# 51_V3.net
KiCad netlist of a schematic drawn in EasyEDA Pro
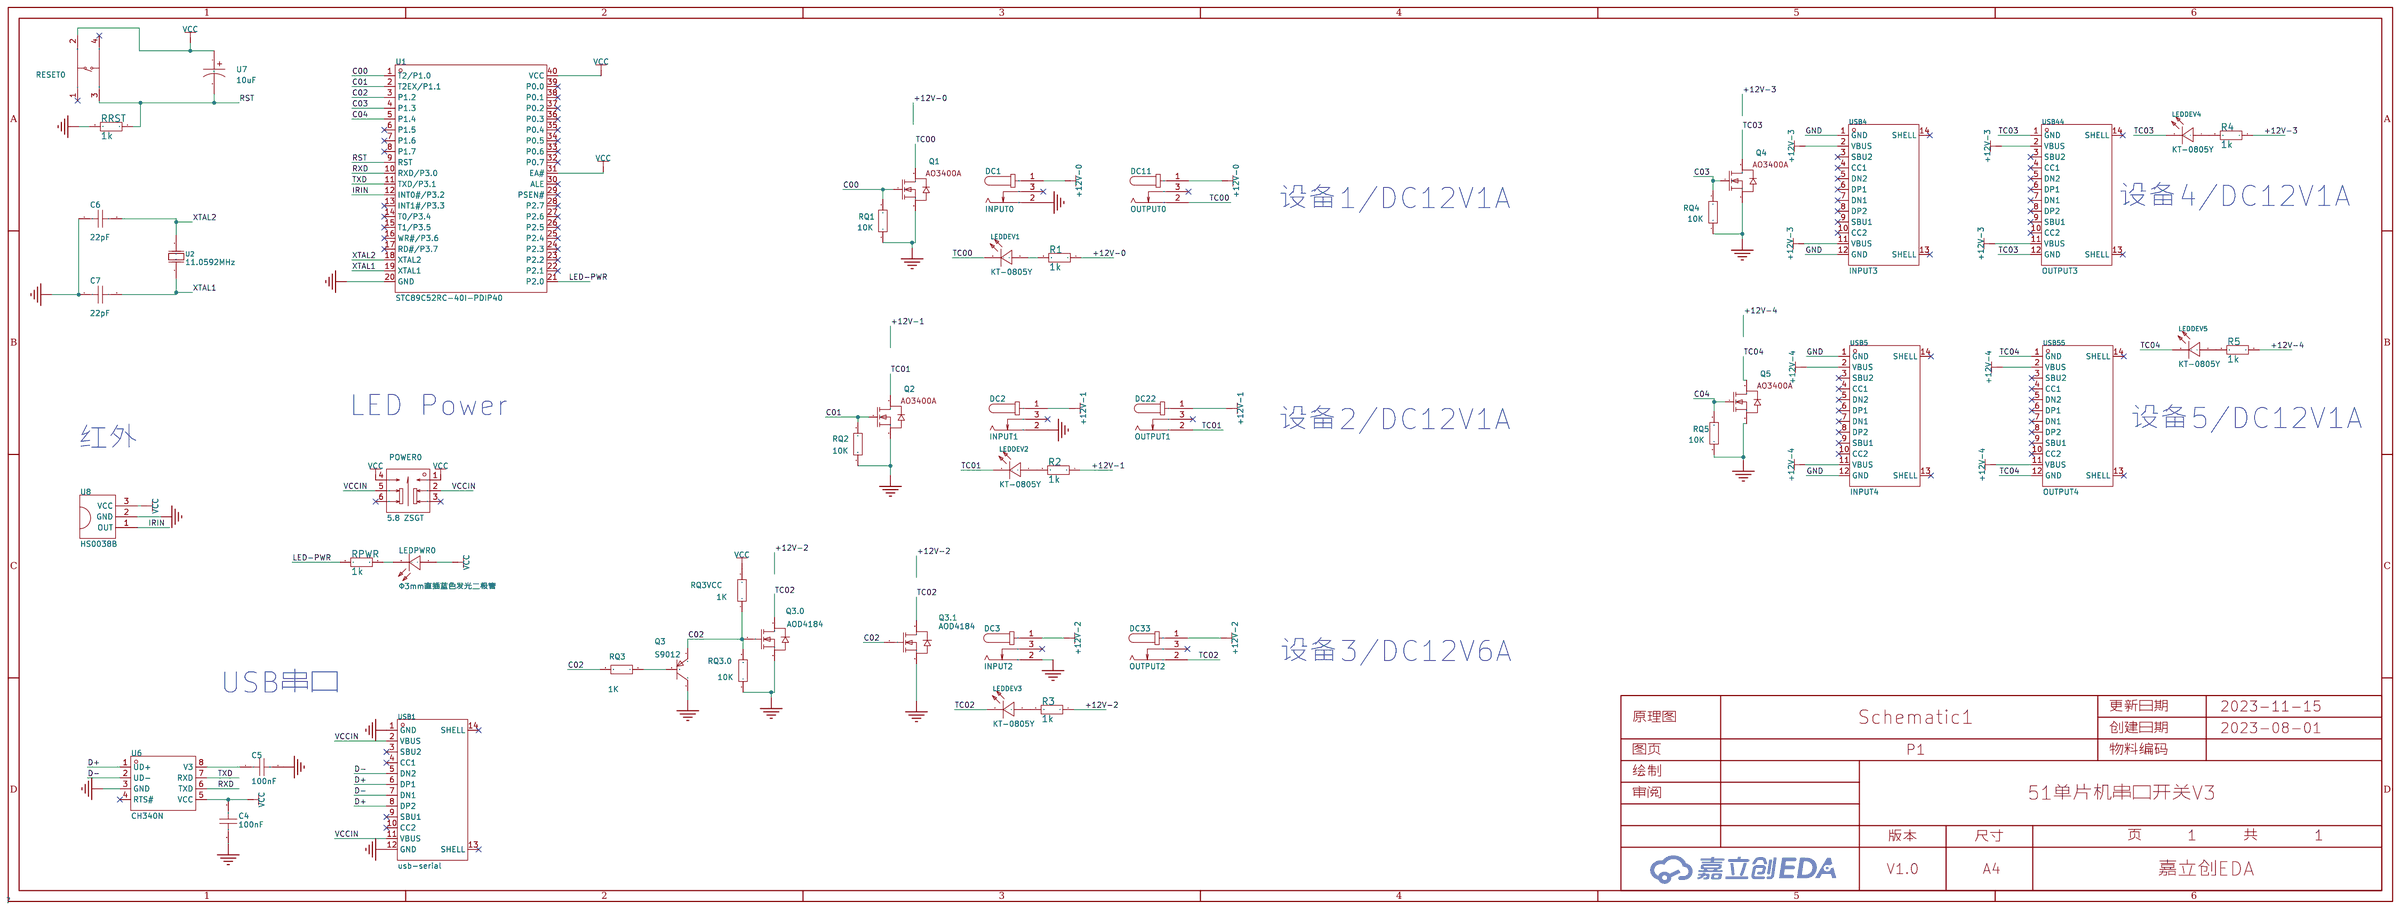
[diagram p0: schematic sheet]

(export (version "E")
  (design (tool "Eeschema 10.0.6"))
  (components
    (comp (ref "C4")
      (value "100nF")
      (footprint "easyedapro:C0603")
      (libsource (lib "easyedapro") (part "CapAcitance"))
    )
    (comp (ref "C5")
      (value "100nF")
      (footprint "easyedapro:C0603")
      (libsource (lib "easyedapro") (part "CapAcitance"))
    )
    (comp (ref "C6")
      (value "22pF")
      (footprint "easyedapro:CAP-TH_L5.8-W2.4-P2.54-D0.6")
      (description "容值:22pF;精度:±10%;额定电压:50V;温度系数:NP0;")
      (fields
        (field (name "Manufacturer Part") "CC1H220KA1EDCH4B1100")
        (field (name "Manufacturer") "Dersonic(德尔创)")
      )
      (libsource (lib "easyedapro") (part "CC1H220KA1EDCH4B1100"))
    )
    (comp (ref "C7")
      (value "22pF")
      (footprint "easyedapro:CAP-TH_L5.8-W2.4-P2.54-D0.6")
      (description "容值:22pF;精度:±10%;额定电压:50V;温度系数:NP0;")
      (fields
        (field (name "Manufacturer Part") "CC1H220KA1EDCH4B1100")
        (field (name "Manufacturer") "Dersonic(德尔创)")
      )
      (libsource (lib "easyedapro") (part "CC1H220KA1EDCH4B1100"))
    )
    (comp (ref "DC1")
      (value "INPUT0")
      (footprint "easyedapro:DC-IN-TH_DC-005-20A")
      (description "触点内径:2mm;触点外径:6.4mm;额定电流:500mA;额定电压:30V;")
      (fields (field (name "Manufacturer Part") "DC-005-20A") (field (name "Manufacturer") "韩国韩荣"))
      (libsource (lib "easyedapro") (part "DC-005-20A_C136744"))
    )
    (comp (ref "DC2")
      (value "INPUT1")
      (footprint "easyedapro:DC-IN-TH_DC-005-20A")
      (description "触点内径:2mm;触点外径:6.4mm;额定电流:500mA;额定电压:30V;")
      (fields (field (name "Manufacturer Part") "DC-005-20A") (field (name "Manufacturer") "韩国韩荣"))
      (libsource (lib "easyedapro") (part "DC-005-20A_C136744"))
    )
    (comp (ref "DC3")
      (value "INPUT2")
      (footprint "easyedapro:DC-IN-TH_DC-005-20A")
      (description "触点内径:2mm;触点外径:6.4mm;额定电流:500mA;额定电压:30V;")
      (fields (field (name "Manufacturer Part") "DC-005-20A") (field (name "Manufacturer") "韩国韩荣"))
      (libsource (lib "easyedapro") (part "DC-005-20A_C136744"))
    )
    (comp (ref "DC11")
      (value "OUTPUT0")
      (footprint "easyedapro:DC-IN-TH_DC-005-20A")
      (description "触点内径:2mm;触点外径:6.4mm;额定电流:500mA;额定电压:30V;")
      (fields (field (name "Manufacturer Part") "DC-005-20A") (field (name "Manufacturer") "韩国韩荣"))
      (libsource (lib "easyedapro") (part "DC-005-20A_C136744"))
    )
    (comp (ref "DC22")
      (value "OUTPUT1")
      (footprint "easyedapro:DC-IN-TH_DC-005-20A")
      (description "触点内径:2mm;触点外径:6.4mm;额定电流:500mA;额定电压:30V;")
      (fields (field (name "Manufacturer Part") "DC-005-20A") (field (name "Manufacturer") "韩国韩荣"))
      (libsource (lib "easyedapro") (part "DC-005-20A_C136744"))
    )
    (comp (ref "DC33")
      (value "OUTPUT2")
      (footprint "easyedapro:DC-IN-TH_DC-005-20A")
      (description "触点内径:2mm;触点外径:6.4mm;额定电流:500mA;额定电压:30V;")
      (fields (field (name "Manufacturer Part") "DC-005-20A") (field (name "Manufacturer") "韩国韩荣"))
      (libsource (lib "easyedapro") (part "DC-005-20A_C136744"))
    )
    (comp (ref "LEDDEV1")
      (value "KT-0805Y")
      (footprint "easyedapro:LED0805-R-RD")
      (description "发光颜色:黄灯;二极管配置:-;透镜颜色:-;主波长:-;色温:-;功率:-;发光角度:-;安装方式:-;工作温度:-;")
      (fields (field (name "Manufacturer") "KENTO"))
      (libsource (lib "easyedapro") (part "17-21SUYC/TR8"))
    )
    (comp (ref "LEDDEV2")
      (value "KT-0805Y")
      (footprint "easyedapro:LED0805-R-RD")
      (description "发光颜色:黄灯;二极管配置:-;透镜颜色:-;主波长:-;色温:-;功率:-;发光角度:-;安装方式:-;工作温度:-;")
      (fields (field (name "Manufacturer") "KENTO"))
      (libsource (lib "easyedapro") (part "17-21SUYC/TR8"))
    )
    (comp (ref "LEDDEV3")
      (value "KT-0805Y")
      (footprint "easyedapro:LED0805-R-RD")
      (description "发光颜色:黄灯;二极管配置:-;透镜颜色:-;主波长:-;色温:-;功率:-;发光角度:-;安装方式:-;工作温度:-;")
      (fields (field (name "Manufacturer") "KENTO"))
      (libsource (lib "easyedapro") (part "17-21SUYC/TR8"))
    )
    (comp (ref "LEDDEV4")
      (value "KT-0805Y")
      (footprint "easyedapro:LED0805-R-RD")
      (description "发光颜色:黄灯;二极管配置:-;透镜颜色:-;主波长:-;色温:-;功率:-;发光角度:-;安装方式:-;工作温度:-;")
      (fields (field (name "Manufacturer") "KENTO"))
      (libsource (lib "easyedapro") (part "17-21SUYC/TR8"))
    )
    (comp (ref "LEDDEV5")
      (value "KT-0805Y")
      (footprint "easyedapro:LED0805-R-RD")
      (description "发光颜色:黄灯;二极管配置:-;透镜颜色:-;主波长:-;色温:-;功率:-;发光角度:-;安装方式:-;工作温度:-;")
      (fields (field (name "Manufacturer") "KENTO"))
      (libsource (lib "easyedapro") (part "17-21SUYC/TR8"))
    )
    (comp (ref "LEDPWR0")
      (value "Φ3mm直插蓝色发光二极管")
      (footprint "easyedapro:LED-TH_BD4.1-P2.50-D0.5-FD_BULE")
      (libsource (lib "easyedapro") (part "Φ3MM直插蓝色发光二极管"))
    )
    (comp (ref "POWER0")
      (value "5.8 ZSGT")
      (footprint "easyedapro:SW-TH_5.8ZSGT")
      (fields (field (name "Manufacturer") "SHOU HAN(首韩)"))
      (libsource (lib "easyedapro") (part "5.8 ZSGT"))
    )
    (comp (ref "Q1")
      (value "AO3400A")
      (footprint "easyedapro:SOT-23-3_L2.9-W1.3-P1.90-LS2.4-BR")
      (description "类型:N沟道;漏源电压(Vdss):30V;连续漏极电流(Id):5.8A;功率(Pd):1.4W;导通电阻(RDS(on)@Vgs,Id):35mΩ@10V,5.8A;")
      (fields (field (name "Manufacturer Part") "AO3400A") (field (name "Manufacturer") "UMW(广东友台半导体)"))
      (libsource (lib "easyedapro") (part "AO3400A_C347475"))
    )
    (comp (ref "Q2")
      (value "AO3400A")
      (footprint "easyedapro:SOT-23-3_L2.9-W1.3-P1.90-LS2.4-BR")
      (description "类型:N沟道;漏源电压(Vdss):30V;连续漏极电流(Id):5.8A;功率(Pd):1.4W;导通电阻(RDS(on)@Vgs,Id):35mΩ@10V,5.8A;")
      (fields (field (name "Manufacturer Part") "AO3400A") (field (name "Manufacturer") "UMW(广东友台半导体)"))
      (libsource (lib "easyedapro") (part "AO3400A_C347475"))
    )
    (comp (ref "Q3")
      (value "S9012")
      (footprint "easyedapro:TO-92-3_L4.6-W3.6-P1.27-L-1")
      (fields (field (name "Manufacturer") "JSMSEMI(杰盛微)"))
      (libsource (lib "easyedapro") (part "S9012_C2931496"))
    )
    (comp (ref "Q3.0")
      (value "AOD4184")
      (footprint "easyedapro:TO-252-2_L6.6-W6.1-P4.58-LS9.9-BR")
      (fields (field (name "Manufacturer") "VBsemi(微碧)"))
      (libsource (lib "easyedapro") (part "AOD4184"))
    )
    (comp (ref "Q3.1")
      (value "AOD4184")
      (footprint "easyedapro:TO-252-2_L6.6-W6.1-P4.58-LS9.9-BR")
      (fields (field (name "Manufacturer") "VBsemi(微碧)"))
      (libsource (lib "easyedapro") (part "AOD4184"))
    )
    (comp (ref "Q4")
      (value "AO3400A")
      (footprint "easyedapro:SOT-23-3_L2.9-W1.3-P1.90-LS2.4-BR")
      (description "类型:N沟道;漏源电压(Vdss):30V;连续漏极电流(Id):5.8A;功率(Pd):1.4W;导通电阻(RDS(on)@Vgs,Id):35mΩ@10V,5.8A;")
      (fields (field (name "Manufacturer Part") "AO3400A") (field (name "Manufacturer") "UMW(广东友台半导体)"))
      (libsource (lib "easyedapro") (part "AO3400A_C347475"))
    )
    (comp (ref "Q5")
      (value "AO3400A")
      (footprint "easyedapro:SOT-23-3_L2.9-W1.3-P1.90-LS2.4-BR")
      (description "类型:N沟道;漏源电压(Vdss):30V;连续漏极电流(Id):5.8A;功率(Pd):1.4W;导通电阻(RDS(on)@Vgs,Id):35mΩ@10V,5.8A;")
      (fields (field (name "Manufacturer Part") "AO3400A") (field (name "Manufacturer") "UMW(广东友台半导体)"))
      (libsource (lib "easyedapro") (part "AO3400A_C347475"))
    )
    (comp (ref "R1")
      (value "1k")
      (footprint "easyedapro:0603")
      (description "Resistor")
      (libsource (lib "easyedapro") (part "RES"))
    )
    (comp (ref "R2")
      (value "1k")
      (footprint "easyedapro:0603")
      (description "Resistor")
      (libsource (lib "easyedapro") (part "RES"))
    )
    (comp (ref "R3")
      (value "1k")
      (footprint "easyedapro:0603")
      (description "Resistor")
      (libsource (lib "easyedapro") (part "RES"))
    )
    (comp (ref "R4")
      (value "1k")
      (footprint "easyedapro:0603")
      (description "Resistor")
      (libsource (lib "easyedapro") (part "RES"))
    )
    (comp (ref "R5")
      (value "1k")
      (footprint "easyedapro:0603")
      (description "Resistor")
      (libsource (lib "easyedapro") (part "RES"))
    )
    (comp (ref "RESET0")
      (value "TS665CJ")
      (footprint "easyedapro:SW-TH_4P-L6.0-W6.0-P4.50-LS6.5")
      (description "触点电流:50mA;额定电压(DC):12V;电路结构:单刀单掷;安装方式:直插;带灯:-;机械寿命:-;")
      (fields (field (name "Manufacturer") "SHOU HAN(首韩)"))
      (libsource (lib "easyedapro") (part "TS665CJ"))
    )
    (comp (ref "RPWR")
      (value "1k")
      (footprint "easyedapro:0603")
      (description "Resistor")
      (libsource (lib "easyedapro") (part "RES"))
    )
    (comp (ref "RQ1") (value "10K") (footprint "easyedapro:R0603") (libsource (lib "easyedapro") (part "电阻")))
    (comp (ref "RQ2") (value "10K") (footprint "easyedapro:R0603") (libsource (lib "easyedapro") (part "电阻")))
    (comp (ref "RQ3") (value "1K") (footprint "easyedapro:R0603") (libsource (lib "easyedapro") (part "电阻")))
    (comp (ref "RQ3.0")
      (value "10K")
      (footprint "easyedapro:R0603")
      (libsource (lib "easyedapro") (part "电阻"))
    )
    (comp (ref "RQ3VCC")
      (value "1K")
      (footprint "easyedapro:R0603")
      (libsource (lib "easyedapro") (part "电阻"))
    )
    (comp (ref "RQ4") (value "10K") (footprint "easyedapro:R0603") (libsource (lib "easyedapro") (part "电阻")))
    (comp (ref "RQ5") (value "10K") (footprint "easyedapro:R0603") (libsource (lib "easyedapro") (part "电阻")))
    (comp (ref "RRST")
      (value "1k")
      (footprint "easyedapro:0603")
      (description "Resistor")
      (libsource (lib "easyedapro") (part "RES"))
    )
    (comp (ref "U1")
      (value "STC89C52RC-40I-PDIP40")
      (footprint "easyedapro:DIP-40_L52.0-W13.7-P2.54-LS15.2-BL")
      (fields (field (name "Manufacturer") "STC(宏晶)"))
      (libsource (lib "easyedapro") (part "STC89C52RC-40I"))
    )
    (comp (ref "U2")
      (value "11.0592MHz")
      (footprint "easyedapro:CRYSTAL-TH_L10.8-W4.5-P4.88")
      (description "频率:10MHz;频率公差:±30ppm;负载电容:18pF;")
      (fields (field (name "Manufacturer Part") "ATS100B-E") (field (name "Manufacturer") "CTS(西迪斯)"))
      (libsource (lib "easyedapro") (part "ATS100B-E"))
    )
    (comp (ref "U6")
      (value "CH340N")
      (footprint "easyedapro:SOP-8_L4.9-W3.9-P1.27-LS6.0-BL")
      (fields (field (name "Manufacturer") "WCH(南京沁恒)"))
      (libsource (lib "easyedapro") (part "CH340N_C2977777"))
    )
    (comp (ref "U7")
      (value "10uF")
      (footprint "easyedapro:CAP-TH_BD6.3-P2.50-D0.5-FD")
      (description "容值:10uF;精度:±20%;额定电压:50V;纹波电流:-;等效串联电阻:-;")
      (fields
        (field (name "Manufacturer Part") "ESK106M1HD11RRSNP-R")
        (field (name "Manufacturer") "MAN YUE(万裕科技)")
      )
      (libsource (lib "easyedapro") (part "ESK106M1HD11RRSNP-R"))
    )
    (comp (ref "U8")
      (value "HS0038B")
      (footprint "easyedapro:OPTO-TH_HS0038B-A")
      (libsource (lib "easyedapro") (part "HS0038B"))
    )
    (comp (ref "USB1")
      (value "usb-serial")
      (footprint "easyedapro:USB-C-SMD_TYPE-C-6PIN-2MD-073")
      (description "连接器类型:Type-C;标准:-;公母:母座;触点数量:16;端口数量:1;安装方式:卧贴;额定电流 - 电源:5A;工作温度范围:-25°C~+85°C;")
      (fields
        (field (name "Manufacturer Part") "TYPE-C 16PIN 2MD(073)")
        (field (name "Manufacturer") "SHOU HAN(首韩)")
      )
      (libsource (lib "easyedapro") (part "TYPE-C 16PIN 2MD(073)"))
    )
    (comp (ref "USB4")
      (value "INPUT3")
      (footprint "easyedapro:USB-C-SMD_TYPE-C-6PIN-2MD-073")
      (description "连接器类型:Type-C;标准:-;公母:母座;触点数量:16;端口数量:1;安装方式:卧贴;额定电流 - 电源:5A;工作温度范围:-25°C~+85°C;")
      (fields
        (field (name "Manufacturer Part") "TYPE-C 16PIN 2MD(073)")
        (field (name "Manufacturer") "SHOU HAN(首韩)")
      )
      (libsource (lib "easyedapro") (part "TYPE-C 16PIN 2MD(073)"))
    )
    (comp (ref "USB5")
      (value "INPUT4")
      (footprint "easyedapro:USB-C-SMD_TYPE-C-6PIN-2MD-073")
      (description "连接器类型:Type-C;标准:-;公母:母座;触点数量:16;端口数量:1;安装方式:卧贴;额定电流 - 电源:5A;工作温度范围:-25°C~+85°C;")
      (fields
        (field (name "Manufacturer Part") "TYPE-C 16PIN 2MD(073)")
        (field (name "Manufacturer") "SHOU HAN(首韩)")
      )
      (libsource (lib "easyedapro") (part "TYPE-C 16PIN 2MD(073)"))
    )
    (comp (ref "USB44")
      (value "OUTPUT3")
      (footprint "easyedapro:USB-C-SMD_TYPE-C-6PIN-2MD-073")
      (description "连接器类型:Type-C;标准:-;公母:母座;触点数量:16;端口数量:1;安装方式:卧贴;额定电流 - 电源:5A;工作温度范围:-25°C~+85°C;")
      (fields
        (field (name "Manufacturer Part") "TYPE-C 16PIN 2MD(073)")
        (field (name "Manufacturer") "SHOU HAN(首韩)")
      )
      (libsource (lib "easyedapro") (part "TYPE-C 16PIN 2MD(073)"))
    )
    (comp (ref "USB55")
      (value "OUTPUT4")
      (footprint "easyedapro:USB-C-SMD_TYPE-C-6PIN-2MD-073")
      (description "连接器类型:Type-C;标准:-;公母:母座;触点数量:16;端口数量:1;安装方式:卧贴;额定电流 - 电源:5A;工作温度范围:-25°C~+85°C;")
      (fields
        (field (name "Manufacturer Part") "TYPE-C 16PIN 2MD(073)")
        (field (name "Manufacturer") "SHOU HAN(首韩)")
      )
      (libsource (lib "easyedapro") (part "TYPE-C 16PIN 2MD(073)"))
    )
  )
  (nets
    (net (code "1") (name "+12V-0") (class "Default")
      (node (ref "DC1") (pin "1") (pinfunction "1_1") (pintype "input"))
      (node (ref "DC11") (pin "1") (pinfunction "1_1") (pintype "input"))
      (node (ref "R1") (pin "1") (pinfunction "1_1") (pintype "input"))
    )
    (net (code "2") (name "+12V-1") (class "Default")
      (node (ref "DC2") (pin "1") (pinfunction "1_1") (pintype "input"))
      (node (ref "DC22") (pin "1") (pinfunction "1_1") (pintype "input"))
      (node (ref "R2") (pin "1") (pinfunction "1_1") (pintype "input"))
    )
    (net (code "3") (name "+12V-2") (class "Default")
      (node (ref "DC3") (pin "1") (pinfunction "1_1") (pintype "input"))
      (node (ref "DC33") (pin "1") (pinfunction "1_1") (pintype "input"))
      (node (ref "R3") (pin "1") (pinfunction "1_1") (pintype "input"))
    )
    (net (code "4") (name "+12V-3") (class "Default")
      (node (ref "R4") (pin "1") (pinfunction "1_1") (pintype "input"))
      (node (ref "USB4") (pin "11") (pinfunction "VBUS_11") (pintype "input"))
      (node (ref "USB4") (pin "2") (pinfunction "VBUS_2") (pintype "input"))
      (node (ref "USB44") (pin "11") (pinfunction "VBUS_11") (pintype "input"))
      (node (ref "USB44") (pin "2") (pinfunction "VBUS_2") (pintype "input"))
    )
    (net (code "5") (name "+12V-4") (class "Default")
      (node (ref "R5") (pin "1") (pinfunction "1_1") (pintype "input"))
      (node (ref "USB5") (pin "11") (pinfunction "VBUS_11") (pintype "input"))
      (node (ref "USB5") (pin "2") (pinfunction "VBUS_2") (pintype "input"))
      (node (ref "USB55") (pin "11") (pinfunction "VBUS_11") (pintype "input"))
      (node (ref "USB55") (pin "2") (pinfunction "VBUS_2") (pintype "input"))
    )
    (net (code "6") (name "/C00") (class "Default")
      (node (ref "Q1") (pin "1") (pinfunction "G_1") (pintype "input"))
      (node (ref "RQ1") (pin "2") (pinfunction "2_2") (pintype "input"))
      (node (ref "U1") (pin "1") (pinfunction "T2/P1.0_1") (pintype "input"))
    )
    (net (code "7") (name "/C01") (class "Default")
      (node (ref "Q2") (pin "1") (pinfunction "G_1") (pintype "input"))
      (node (ref "RQ2") (pin "2") (pinfunction "2_2") (pintype "input"))
      (node (ref "U1") (pin "2") (pinfunction "T2EX/P1.1_2") (pintype "input"))
    )
    (net (code "8") (name "/C02") (class "Default")
      (node (ref "Q3") (pin "1") (pinfunction "E_1") (pintype "input"))
      (node (ref "Q3.0") (pin "1") (pinfunction "G_1") (pintype "input"))
      (node (ref "Q3.1") (pin "1") (pinfunction "G_1") (pintype "input"))
      (node (ref "RQ3") (pin "2") (pinfunction "2_2") (pintype "input"))
      (node (ref "RQ3.0") (pin "2") (pinfunction "2_2") (pintype "input"))
      (node (ref "RQ3VCC") (pin "1") (pinfunction "1_1") (pintype "input"))
      (node (ref "U1") (pin "3") (pinfunction "P1.2_3") (pintype "input"))
    )
    (net (code "9") (name "/C03") (class "Default")
      (node (ref "Q4") (pin "1") (pinfunction "G_1") (pintype "input"))
      (node (ref "RQ4") (pin "2") (pinfunction "2_2") (pintype "input"))
      (node (ref "U1") (pin "4") (pinfunction "P1.3_4") (pintype "input"))
    )
    (net (code "10") (name "/C04") (class "Default")
      (node (ref "Q5") (pin "1") (pinfunction "G_1") (pintype "input"))
      (node (ref "RQ5") (pin "2") (pinfunction "2_2") (pintype "input"))
      (node (ref "U1") (pin "5") (pinfunction "P1.4_5") (pintype "input"))
    )
    (net (code "11") (name "/D+") (class "Default")
      (node (ref "U6") (pin "1") (pinfunction "UD+_1") (pintype "input"))
      (node (ref "USB1") (pin "6") (pinfunction "DP1_6") (pintype "input"))
      (node (ref "USB1") (pin "8") (pinfunction "DP2_8") (pintype "input"))
    )
    (net (code "12") (name "/D-") (class "Default")
      (node (ref "U6") (pin "2") (pinfunction "UD-_2") (pintype "input"))
      (node (ref "USB1") (pin "5") (pinfunction "DN2_5") (pintype "input"))
      (node (ref "USB1") (pin "7") (pinfunction "DN1_7") (pintype "input"))
    )
    (net (code "13") (name "/IRIN") (class "Default")
      (node (ref "U1") (pin "12") (pinfunction "INT0#/P3.2_12") (pintype "input"))
      (node (ref "U8") (pin "1") (pinfunction "OUT_1") (pintype "input"))
    )
    (net (code "14") (name "/LED-PWR") (class "Default")
      (node (ref "RPWR") (pin "2") (pinfunction "2_2") (pintype "input"))
      (node (ref "U1") (pin "21") (pinfunction "P2.0_21") (pintype "input"))
    )
    (net (code "15") (name "/RST") (class "Default")
      (node (ref "RESET0") (pin "3") (pinfunction "C_3") (pintype "input"))
      (node (ref "RRST") (pin "1") (pinfunction "1_1") (pintype "input"))
      (node (ref "U1") (pin "9") (pinfunction "RST_9") (pintype "input"))
      (node (ref "U7") (pin "2") (pinfunction "2_2") (pintype "input"))
    )
    (net (code "16") (name "/RXD") (class "Default")
      (node (ref "U1") (pin "10") (pinfunction "RXD/P3.0_10") (pintype "input"))
      (node (ref "U6") (pin "6") (pinfunction "TXD_6") (pintype "input"))
    )
    (net (code "17") (name "/TC00") (class "Default")
      (node (ref "DC11") (pin "2") (pinfunction "2_2") (pintype "input"))
      (node (ref "LEDDEV1") (pin "2") (pinfunction "-_2") (pintype "input"))
      (node (ref "Q1") (pin "3") (pinfunction "D_3") (pintype "input"))
    )
    (net (code "18") (name "/TC01") (class "Default")
      (node (ref "DC22") (pin "2") (pinfunction "2_2") (pintype "input"))
      (node (ref "LEDDEV2") (pin "2") (pinfunction "-_2") (pintype "input"))
      (node (ref "Q2") (pin "3") (pinfunction "D_3") (pintype "input"))
    )
    (net (code "19") (name "/TC02") (class "Default")
      (node (ref "DC33") (pin "2") (pinfunction "2_2") (pintype "input"))
      (node (ref "LEDDEV3") (pin "2") (pinfunction "-_2") (pintype "input"))
      (node (ref "Q3.0") (pin "2") (pinfunction "D_2") (pintype "input"))
      (node (ref "Q3.1") (pin "2") (pinfunction "D_2") (pintype "input"))
    )
    (net (code "20") (name "/TC03") (class "Default")
      (node (ref "LEDDEV4") (pin "2") (pinfunction "-_2") (pintype "input"))
      (node (ref "Q4") (pin "3") (pinfunction "D_3") (pintype "input"))
      (node (ref "USB44") (pin "1") (pinfunction "GND_1") (pintype "input"))
      (node (ref "USB44") (pin "12") (pinfunction "GND_12") (pintype "input"))
    )
    (net (code "21") (name "/TC04") (class "Default")
      (node (ref "LEDDEV5") (pin "2") (pinfunction "-_2") (pintype "input"))
      (node (ref "Q5") (pin "3") (pinfunction "D_3") (pintype "input"))
      (node (ref "USB55") (pin "1") (pinfunction "GND_1") (pintype "input"))
      (node (ref "USB55") (pin "12") (pinfunction "GND_12") (pintype "input"))
    )
    (net (code "22") (name "/TXD") (class "Default")
      (node (ref "U1") (pin "11") (pinfunction "TXD/P3.1_11") (pintype "input"))
      (node (ref "U6") (pin "7") (pinfunction "RXD_7") (pintype "input"))
    )
    (net (code "23") (name "/VCCIN") (class "Default")
      (node (ref "POWER0") (pin "2") (pinfunction "2_2") (pintype "input"))
      (node (ref "POWER0") (pin "5") (pinfunction "5_5") (pintype "input"))
      (node (ref "USB1") (pin "11") (pinfunction "VBUS_11") (pintype "input"))
      (node (ref "USB1") (pin "2") (pinfunction "VBUS_2") (pintype "input"))
    )
    (net (code "24") (name "/XTAL1") (class "Default")
      (node (ref "C7") (pin "2") (pinfunction "2_2") (pintype "input"))
      (node (ref "U1") (pin "19") (pinfunction "XTAL1_19") (pintype "input"))
      (node (ref "U2") (pin "2") (pinfunction "2_2") (pintype "input"))
    )
    (net (code "25") (name "/XTAL2") (class "Default")
      (node (ref "C6") (pin "2") (pinfunction "2_2") (pintype "input"))
      (node (ref "U1") (pin "18") (pinfunction "XTAL2_18") (pintype "input"))
      (node (ref "U2") (pin "1") (pinfunction "1_1") (pintype "input"))
    )
    (net (code "26") (name "GND") (class "Default")
      (node (ref "C4") (pin "2") (pinfunction "2_2") (pintype "input"))
      (node (ref "C5") (pin "2") (pinfunction "2_2") (pintype "input"))
      (node (ref "C6") (pin "1") (pinfunction "1_1") (pintype "input"))
      (node (ref "C7") (pin "1") (pinfunction "1_1") (pintype "input"))
      (node (ref "DC1") (pin "2") (pinfunction "2_2") (pintype "input"))
      (node (ref "DC2") (pin "2") (pinfunction "2_2") (pintype "input"))
      (node (ref "DC3") (pin "2") (pinfunction "2_2") (pintype "input"))
      (node (ref "Q1") (pin "2") (pinfunction "S_2") (pintype "input"))
      (node (ref "Q2") (pin "2") (pinfunction "S_2") (pintype "input"))
      (node (ref "Q3") (pin "3") (pinfunction "C_3") (pintype "input"))
      (node (ref "Q3.0") (pin "3") (pinfunction "S_3") (pintype "input"))
      (node (ref "Q3.1") (pin "3") (pinfunction "S_3") (pintype "input"))
      (node (ref "Q4") (pin "2") (pinfunction "S_2") (pintype "input"))
      (node (ref "Q5") (pin "2") (pinfunction "S_2") (pintype "input"))
      (node (ref "RQ1") (pin "1") (pinfunction "1_1") (pintype "input"))
      (node (ref "RQ2") (pin "1") (pinfunction "1_1") (pintype "input"))
      (node (ref "RQ3.0") (pin "1") (pinfunction "1_1") (pintype "input"))
      (node (ref "RQ4") (pin "1") (pinfunction "1_1") (pintype "input"))
      (node (ref "RQ5") (pin "1") (pinfunction "1_1") (pintype "input"))
      (node (ref "RRST") (pin "2") (pinfunction "2_2") (pintype "input"))
      (node (ref "U1") (pin "20") (pinfunction "GND_20") (pintype "input"))
      (node (ref "U6") (pin "3") (pinfunction "GND_3") (pintype "input"))
      (node (ref "U8") (pin "2") (pinfunction "GND_2") (pintype "input"))
      (node (ref "USB1") (pin "1") (pinfunction "GND_1") (pintype "input"))
      (node (ref "USB1") (pin "12") (pinfunction "GND_12") (pintype "input"))
      (node (ref "USB4") (pin "1") (pinfunction "GND_1") (pintype "input"))
      (node (ref "USB4") (pin "12") (pinfunction "GND_12") (pintype "input"))
      (node (ref "USB5") (pin "1") (pinfunction "GND_1") (pintype "input"))
      (node (ref "USB5") (pin "12") (pinfunction "GND_12") (pintype "input"))
    )
    (net (code "27") (name "Net-(LEDDEV1-+)") (class "Default")
      (node (ref "LEDDEV1") (pin "1") (pinfunction "+_1") (pintype "input"))
      (node (ref "R1") (pin "2") (pinfunction "2_2") (pintype "input"))
    )
    (net (code "28") (name "Net-(LEDDEV2-+)") (class "Default")
      (node (ref "LEDDEV2") (pin "1") (pinfunction "+_1") (pintype "input"))
      (node (ref "R2") (pin "2") (pinfunction "2_2") (pintype "input"))
    )
    (net (code "29") (name "Net-(LEDDEV3-+)") (class "Default")
      (node (ref "LEDDEV3") (pin "1") (pinfunction "+_1") (pintype "input"))
      (node (ref "R3") (pin "2") (pinfunction "2_2") (pintype "input"))
    )
    (net (code "30") (name "Net-(LEDDEV4-+)") (class "Default")
      (node (ref "LEDDEV4") (pin "1") (pinfunction "+_1") (pintype "input"))
      (node (ref "R4") (pin "2") (pinfunction "2_2") (pintype "input"))
    )
    (net (code "31") (name "Net-(LEDDEV5-+)") (class "Default")
      (node (ref "LEDDEV5") (pin "1") (pinfunction "+_1") (pintype "input"))
      (node (ref "R5") (pin "2") (pinfunction "2_2") (pintype "input"))
    )
    (net (code "32") (name "Net-(LEDPWR0--)") (class "Default")
      (node (ref "LEDPWR0") (pin "2") (pinfunction "-_2") (pintype "input"))
      (node (ref "RPWR") (pin "1") (pinfunction "1_1") (pintype "input"))
    )
    (net (code "33") (name "Net-(Q3-B)") (class "Default")
      (node (ref "Q3") (pin "2") (pinfunction "B_2") (pintype "input"))
      (node (ref "RQ3") (pin "1") (pinfunction "1_1") (pintype "input"))
    )
    (net (code "34") (name "Net-(U6-V3)") (class "Default")
      (node (ref "C5") (pin "1") (pinfunction "1_1") (pintype "input"))
      (node (ref "U6") (pin "8") (pinfunction "V3_8") (pintype "input"))
    )
    (net (code "35") (name "VCC") (class "Default")
      (node (ref "C4") (pin "1") (pinfunction "1_1") (pintype "input"))
      (node (ref "LEDPWR0") (pin "1") (pinfunction "+_1") (pintype "input"))
      (node (ref "POWER0") (pin "1") (pinfunction "1_1") (pintype "input"))
      (node (ref "POWER0") (pin "4") (pinfunction "4_4") (pintype "input"))
      (node (ref "RESET0") (pin "2") (pinfunction "B_2") (pintype "input"))
      (node (ref "RQ3VCC") (pin "2") (pinfunction "2_2") (pintype "input"))
      (node (ref "U1") (pin "31") (pinfunction "EA#_31") (pintype "input"))
      (node (ref "U1") (pin "40") (pinfunction "VCC_40") (pintype "input"))
      (node (ref "U6") (pin "5") (pinfunction "VCC_5") (pintype "input"))
      (node (ref "U7") (pin "1") (pinfunction "1_1") (pintype "input"))
      (node (ref "U8") (pin "3") (pinfunction "VCC_3") (pintype "input"))
    )
    (net (code "36") (name "unconnected-(DC1-Pad3)") (class "Default")
      (node (ref "DC1") (pin "3") (pinfunction "3_3") (pintype "input+no_connect"))
    )
    (net (code "37") (name "unconnected-(DC2-Pad3)") (class "Default")
      (node (ref "DC2") (pin "3") (pinfunction "3_3") (pintype "input+no_connect"))
    )
    (net (code "38") (name "unconnected-(DC3-Pad3)") (class "Default")
      (node (ref "DC3") (pin "3") (pinfunction "3_3") (pintype "input+no_connect"))
    )
    (net (code "39") (name "unconnected-(DC11-Pad3)") (class "Default")
      (node (ref "DC11") (pin "3") (pinfunction "3_3") (pintype "input+no_connect"))
    )
    (net (code "40") (name "unconnected-(DC22-Pad3)") (class "Default")
      (node (ref "DC22") (pin "3") (pinfunction "3_3") (pintype "input+no_connect"))
    )
    (net (code "41") (name "unconnected-(DC33-Pad3)") (class "Default")
      (node (ref "DC33") (pin "3") (pinfunction "3_3") (pintype "input+no_connect"))
    )
    (net (code "42") (name "unconnected-(POWER0-Pad3)") (class "Default")
      (node (ref "POWER0") (pin "3") (pinfunction "3_3") (pintype "input+no_connect"))
    )
    (net (code "43") (name "unconnected-(POWER0-Pad6)") (class "Default")
      (node (ref "POWER0") (pin "6") (pinfunction "6_6") (pintype "input+no_connect"))
    )
    (net (code "44") (name "unconnected-(RESET0-A-Pad1)") (class "Default")
      (node (ref "RESET0") (pin "1") (pinfunction "A_1") (pintype "input+no_connect"))
    )
    (net (code "45") (name "unconnected-(RESET0-D-Pad4)") (class "Default")
      (node (ref "RESET0") (pin "4") (pinfunction "D_4") (pintype "input+no_connect"))
    )
    (net (code "46") (name "unconnected-(U1-ALE-Pad30)") (class "Default")
      (node (ref "U1") (pin "30") (pinfunction "ALE_30") (pintype "input+no_connect"))
    )
    (net (code "47") (name "unconnected-(U1-INT1#{slash}P3.3-Pad13)") (class "Default")
      (node (ref "U1") (pin "13") (pinfunction "INT1#/P3.3_13") (pintype "input+no_connect"))
    )
    (net (code "48") (name "unconnected-(U1-P0.0-Pad39)") (class "Default")
      (node (ref "U1") (pin "39") (pinfunction "P0.0_39") (pintype "input+no_connect"))
    )
    (net (code "49") (name "unconnected-(U1-P0.1-Pad38)") (class "Default")
      (node (ref "U1") (pin "38") (pinfunction "P0.1_38") (pintype "input+no_connect"))
    )
    (net (code "50") (name "unconnected-(U1-P0.2-Pad37)") (class "Default")
      (node (ref "U1") (pin "37") (pinfunction "P0.2_37") (pintype "input+no_connect"))
    )
    (net (code "51") (name "unconnected-(U1-P0.3-Pad36)") (class "Default")
      (node (ref "U1") (pin "36") (pinfunction "P0.3_36") (pintype "input+no_connect"))
    )
    (net (code "52") (name "unconnected-(U1-P0.4-Pad35)") (class "Default")
      (node (ref "U1") (pin "35") (pinfunction "P0.4_35") (pintype "input+no_connect"))
    )
    (net (code "53") (name "unconnected-(U1-P0.5-Pad34)") (class "Default")
      (node (ref "U1") (pin "34") (pinfunction "P0.5_34") (pintype "input+no_connect"))
    )
    (net (code "54") (name "unconnected-(U1-P0.6-Pad33)") (class "Default")
      (node (ref "U1") (pin "33") (pinfunction "P0.6_33") (pintype "input+no_connect"))
    )
    (net (code "55") (name "unconnected-(U1-P0.7-Pad32)") (class "Default")
      (node (ref "U1") (pin "32") (pinfunction "P0.7_32") (pintype "input+no_connect"))
    )
    (net (code "56") (name "unconnected-(U1-P1.5-Pad6)") (class "Default")
      (node (ref "U1") (pin "6") (pinfunction "P1.5_6") (pintype "input+no_connect"))
    )
    (net (code "57") (name "unconnected-(U1-P1.6-Pad7)") (class "Default")
      (node (ref "U1") (pin "7") (pinfunction "P1.6_7") (pintype "input+no_connect"))
    )
    (net (code "58") (name "unconnected-(U1-P1.7-Pad8)") (class "Default")
      (node (ref "U1") (pin "8") (pinfunction "P1.7_8") (pintype "input+no_connect"))
    )
    (net (code "59") (name "unconnected-(U1-P2.1-Pad22)") (class "Default")
      (node (ref "U1") (pin "22") (pinfunction "P2.1_22") (pintype "input+no_connect"))
    )
    (net (code "60") (name "unconnected-(U1-P2.2-Pad23)") (class "Default")
      (node (ref "U1") (pin "23") (pinfunction "P2.2_23") (pintype "input+no_connect"))
    )
    (net (code "61") (name "unconnected-(U1-P2.3-Pad24)") (class "Default")
      (node (ref "U1") (pin "24") (pinfunction "P2.3_24") (pintype "input+no_connect"))
    )
    (net (code "62") (name "unconnected-(U1-P2.4-Pad25)") (class "Default")
      (node (ref "U1") (pin "25") (pinfunction "P2.4_25") (pintype "input+no_connect"))
    )
    (net (code "63") (name "unconnected-(U1-P2.5-Pad26)") (class "Default")
      (node (ref "U1") (pin "26") (pinfunction "P2.5_26") (pintype "input+no_connect"))
    )
    (net (code "64") (name "unconnected-(U1-P2.6-Pad27)") (class "Default")
      (node (ref "U1") (pin "27") (pinfunction "P2.6_27") (pintype "input+no_connect"))
    )
    (net (code "65") (name "unconnected-(U1-P2.7-Pad28)") (class "Default")
      (node (ref "U1") (pin "28") (pinfunction "P2.7_28") (pintype "input+no_connect"))
    )
    (net (code "66") (name "unconnected-(U1-PSEN#-Pad29)") (class "Default")
      (node (ref "U1") (pin "29") (pinfunction "PSEN#_29") (pintype "input+no_connect"))
    )
    (net (code "67") (name "unconnected-(U1-RD#{slash}P3.7-Pad17)") (class "Default")
      (node (ref "U1") (pin "17") (pinfunction "RD#/P3.7_17") (pintype "input+no_connect"))
    )
    (net (code "68") (name "unconnected-(U1-T0{slash}P3.4-Pad14)") (class "Default")
      (node (ref "U1") (pin "14") (pinfunction "T0/P3.4_14") (pintype "input+no_connect"))
    )
    (net (code "69") (name "unconnected-(U1-T1{slash}P3.5-Pad15)") (class "Default")
      (node (ref "U1") (pin "15") (pinfunction "T1/P3.5_15") (pintype "input+no_connect"))
    )
    (net (code "70") (name "unconnected-(U1-WR#{slash}P3.6-Pad16)") (class "Default")
      (node (ref "U1") (pin "16") (pinfunction "WR#/P3.6_16") (pintype "input+no_connect"))
    )
    (net (code "71") (name "unconnected-(U6-RTS#-Pad4)") (class "Default")
      (node (ref "U6") (pin "4") (pinfunction "RTS#_4") (pintype "input+no_connect"))
    )
    (net (code "72") (name "unconnected-(USB1-CC1-Pad4)") (class "Default")
      (node (ref "USB1") (pin "4") (pinfunction "CC1_4") (pintype "input+no_connect"))
    )
    (net (code "73") (name "unconnected-(USB1-CC2-Pad10)") (class "Default")
      (node (ref "USB1") (pin "10") (pinfunction "CC2_10") (pintype "input+no_connect"))
    )
    (net (code "74") (name "unconnected-(USB1-SBU1-Pad9)") (class "Default")
      (node (ref "USB1") (pin "9") (pinfunction "SBU1_9") (pintype "input+no_connect"))
    )
    (net (code "75") (name "unconnected-(USB1-SBU2-Pad3)") (class "Default")
      (node (ref "USB1") (pin "3") (pinfunction "SBU2_3") (pintype "input+no_connect"))
    )
    (net (code "76") (name "unconnected-(USB1-SHELL-Pad13)") (class "Default")
      (node (ref "USB1") (pin "13") (pinfunction "SHELL_13") (pintype "input+no_connect"))
    )
    (net (code "77") (name "unconnected-(USB1-SHELL-Pad14)") (class "Default")
      (node (ref "USB1") (pin "14") (pinfunction "SHELL_14") (pintype "input+no_connect"))
    )
    (net (code "78") (name "unconnected-(USB4-CC1-Pad4)") (class "Default")
      (node (ref "USB4") (pin "4") (pinfunction "CC1_4") (pintype "input+no_connect"))
    )
    (net (code "79") (name "unconnected-(USB4-CC2-Pad10)") (class "Default")
      (node (ref "USB4") (pin "10") (pinfunction "CC2_10") (pintype "input+no_connect"))
    )
    (net (code "80") (name "unconnected-(USB4-DN1-Pad7)") (class "Default")
      (node (ref "USB4") (pin "7") (pinfunction "DN1_7") (pintype "input+no_connect"))
    )
    (net (code "81") (name "unconnected-(USB4-DN2-Pad5)") (class "Default")
      (node (ref "USB4") (pin "5") (pinfunction "DN2_5") (pintype "input+no_connect"))
    )
    (net (code "82") (name "unconnected-(USB4-DP1-Pad6)") (class "Default")
      (node (ref "USB4") (pin "6") (pinfunction "DP1_6") (pintype "input+no_connect"))
    )
    (net (code "83") (name "unconnected-(USB4-DP2-Pad8)") (class "Default")
      (node (ref "USB4") (pin "8") (pinfunction "DP2_8") (pintype "input+no_connect"))
    )
    (net (code "84") (name "unconnected-(USB4-SBU1-Pad9)") (class "Default")
      (node (ref "USB4") (pin "9") (pinfunction "SBU1_9") (pintype "input+no_connect"))
    )
    (net (code "85") (name "unconnected-(USB4-SBU2-Pad3)") (class "Default")
      (node (ref "USB4") (pin "3") (pinfunction "SBU2_3") (pintype "input+no_connect"))
    )
    (net (code "86") (name "unconnected-(USB4-SHELL-Pad13)") (class "Default")
      (node (ref "USB4") (pin "13") (pinfunction "SHELL_13") (pintype "input+no_connect"))
    )
    (net (code "87") (name "unconnected-(USB4-SHELL-Pad14)") (class "Default")
      (node (ref "USB4") (pin "14") (pinfunction "SHELL_14") (pintype "input+no_connect"))
    )
    (net (code "88") (name "unconnected-(USB5-CC1-Pad4)") (class "Default")
      (node (ref "USB5") (pin "4") (pinfunction "CC1_4") (pintype "input+no_connect"))
    )
    (net (code "89") (name "unconnected-(USB5-CC2-Pad10)") (class "Default")
      (node (ref "USB5") (pin "10") (pinfunction "CC2_10") (pintype "input+no_connect"))
    )
    (net (code "90") (name "unconnected-(USB5-DN1-Pad7)") (class "Default")
      (node (ref "USB5") (pin "7") (pinfunction "DN1_7") (pintype "input+no_connect"))
    )
    (net (code "91") (name "unconnected-(USB5-DN2-Pad5)") (class "Default")
      (node (ref "USB5") (pin "5") (pinfunction "DN2_5") (pintype "input+no_connect"))
    )
    (net (code "92") (name "unconnected-(USB5-DP1-Pad6)") (class "Default")
      (node (ref "USB5") (pin "6") (pinfunction "DP1_6") (pintype "input+no_connect"))
    )
    (net (code "93") (name "unconnected-(USB5-DP2-Pad8)") (class "Default")
      (node (ref "USB5") (pin "8") (pinfunction "DP2_8") (pintype "input+no_connect"))
    )
    (net (code "94") (name "unconnected-(USB5-SBU1-Pad9)") (class "Default")
      (node (ref "USB5") (pin "9") (pinfunction "SBU1_9") (pintype "input+no_connect"))
    )
    (net (code "95") (name "unconnected-(USB5-SBU2-Pad3)") (class "Default")
      (node (ref "USB5") (pin "3") (pinfunction "SBU2_3") (pintype "input+no_connect"))
    )
    (net (code "96") (name "unconnected-(USB5-SHELL-Pad13)") (class "Default")
      (node (ref "USB5") (pin "13") (pinfunction "SHELL_13") (pintype "input+no_connect"))
    )
    (net (code "97") (name "unconnected-(USB5-SHELL-Pad14)") (class "Default")
      (node (ref "USB5") (pin "14") (pinfunction "SHELL_14") (pintype "input+no_connect"))
    )
    (net (code "98") (name "unconnected-(USB44-CC1-Pad4)") (class "Default")
      (node (ref "USB44") (pin "4") (pinfunction "CC1_4") (pintype "input+no_connect"))
    )
    (net (code "99") (name "unconnected-(USB44-CC2-Pad10)") (class "Default")
      (node (ref "USB44") (pin "10") (pinfunction "CC2_10") (pintype "input+no_connect"))
    )
    (net (code "100") (name "unconnected-(USB44-DN1-Pad7)") (class "Default")
      (node (ref "USB44") (pin "7") (pinfunction "DN1_7") (pintype "input+no_connect"))
    )
    (net (code "101") (name "unconnected-(USB44-DN2-Pad5)") (class "Default")
      (node (ref "USB44") (pin "5") (pinfunction "DN2_5") (pintype "input+no_connect"))
    )
    (net (code "102") (name "unconnected-(USB44-DP1-Pad6)") (class "Default")
      (node (ref "USB44") (pin "6") (pinfunction "DP1_6") (pintype "input+no_connect"))
    )
    (net (code "103") (name "unconnected-(USB44-DP2-Pad8)") (class "Default")
      (node (ref "USB44") (pin "8") (pinfunction "DP2_8") (pintype "input+no_connect"))
    )
    (net (code "104") (name "unconnected-(USB44-SBU1-Pad9)") (class "Default")
      (node (ref "USB44") (pin "9") (pinfunction "SBU1_9") (pintype "input+no_connect"))
    )
    (net (code "105") (name "unconnected-(USB44-SBU2-Pad3)") (class "Default")
      (node (ref "USB44") (pin "3") (pinfunction "SBU2_3") (pintype "input+no_connect"))
    )
    (net (code "106") (name "unconnected-(USB44-SHELL-Pad13)") (class "Default")
      (node (ref "USB44") (pin "13") (pinfunction "SHELL_13") (pintype "input+no_connect"))
    )
    (net (code "107") (name "unconnected-(USB44-SHELL-Pad14)") (class "Default")
      (node (ref "USB44") (pin "14") (pinfunction "SHELL_14") (pintype "input+no_connect"))
    )
    (net (code "108") (name "unconnected-(USB55-CC1-Pad4)") (class "Default")
      (node (ref "USB55") (pin "4") (pinfunction "CC1_4") (pintype "input+no_connect"))
    )
    (net (code "109") (name "unconnected-(USB55-CC2-Pad10)") (class "Default")
      (node (ref "USB55") (pin "10") (pinfunction "CC2_10") (pintype "input+no_connect"))
    )
    (net (code "110") (name "unconnected-(USB55-DN1-Pad7)") (class "Default")
      (node (ref "USB55") (pin "7") (pinfunction "DN1_7") (pintype "input+no_connect"))
    )
    (net (code "111") (name "unconnected-(USB55-DN2-Pad5)") (class "Default")
      (node (ref "USB55") (pin "5") (pinfunction "DN2_5") (pintype "input+no_connect"))
    )
    (net (code "112") (name "unconnected-(USB55-DP1-Pad6)") (class "Default")
      (node (ref "USB55") (pin "6") (pinfunction "DP1_6") (pintype "input+no_connect"))
    )
    (net (code "113") (name "unconnected-(USB55-DP2-Pad8)") (class "Default")
      (node (ref "USB55") (pin "8") (pinfunction "DP2_8") (pintype "input+no_connect"))
    )
    (net (code "114") (name "unconnected-(USB55-SBU1-Pad9)") (class "Default")
      (node (ref "USB55") (pin "9") (pinfunction "SBU1_9") (pintype "input+no_connect"))
    )
    (net (code "115") (name "unconnected-(USB55-SBU2-Pad3)") (class "Default")
      (node (ref "USB55") (pin "3") (pinfunction "SBU2_3") (pintype "input+no_connect"))
    )
    (net (code "116") (name "unconnected-(USB55-SHELL-Pad13)") (class "Default")
      (node (ref "USB55") (pin "13") (pinfunction "SHELL_13") (pintype "input+no_connect"))
    )
    (net (code "117") (name "unconnected-(USB55-SHELL-Pad14)") (class "Default")
      (node (ref "USB55") (pin "14") (pinfunction "SHELL_14") (pintype "input+no_connect"))
    )
  )
)
